# CAL_JIG.net
KiCad netlist of a schematic drawn in Altium Designer
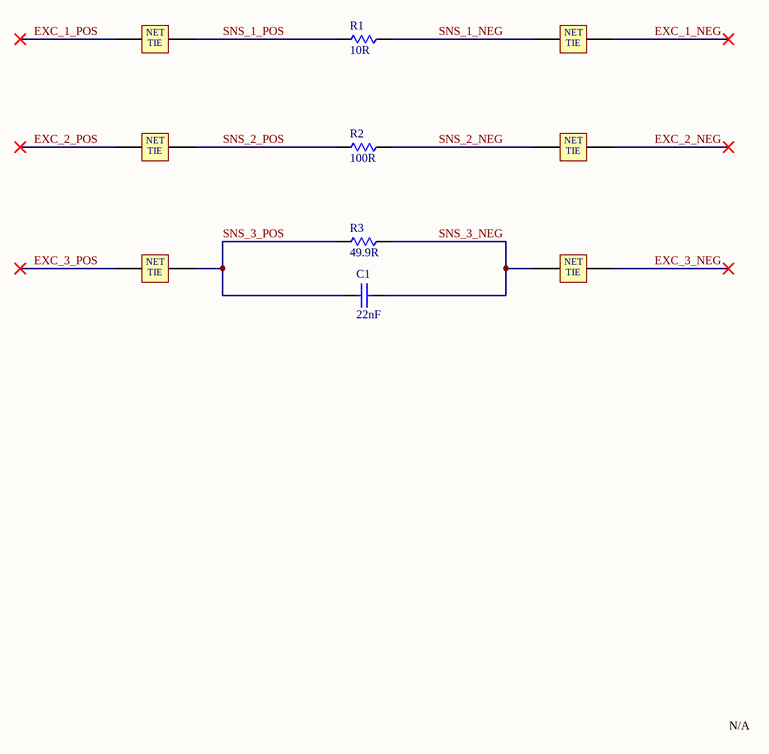
[diagram p0: CAL JIG.SchDoc]

(export (version "E")
  (design (tool "Eeschema 10.0.6"))
  (components
    (comp (ref "C1")
      (value "22nF")
      (footprint "0603-CAP")
      (description "CAP CER 470PF 50V NPO 0603")
      (libsource (lib "SGL_Capacitors") (part "Capacitor"))
    )
    (comp (ref "NT1")
      (value "Net Tie")
      (footprint "Net Tie 10mil")
      (description "Tying two nets")
      (libsource (lib "SGL_Misc") (part "Net Tie"))
    )
    (comp (ref "NT2")
      (value "Net Tie")
      (footprint "Net Tie 10mil")
      (description "Tying two nets")
      (libsource (lib "SGL_Misc") (part "Net Tie"))
    )
    (comp (ref "NT3")
      (value "Net Tie")
      (footprint "Net Tie 10mil")
      (description "Tying two nets")
      (libsource (lib "SGL_Misc") (part "Net Tie"))
    )
    (comp (ref "NT4")
      (value "Net Tie")
      (footprint "Net Tie 10mil")
      (description "Tying two nets")
      (libsource (lib "SGL_Misc") (part "Net Tie"))
    )
    (comp (ref "NT5")
      (value "Net Tie")
      (footprint "Net Tie 10mil")
      (description "Tying two nets")
      (libsource (lib "SGL_Misc") (part "Net Tie"))
    )
    (comp (ref "NT6")
      (value "Net Tie")
      (footprint "Net Tie 10mil")
      (description "Tying two nets")
      (libsource (lib "SGL_Misc") (part "Net Tie"))
    )
    (comp (ref "R1")
      (value "10R")
      (footprint "0603-RES")
      (description "RES SMD 1K OHM 1% 1/10W 0603")
      (libsource (lib "SGL_Resistives") (part "RESISTOR"))
    )
    (comp (ref "R2")
      (value "100R")
      (footprint "0603-RES")
      (description "RES SMD 1K OHM 1% 1/10W 0603")
      (libsource (lib "SGL_Resistives") (part "RESISTOR"))
    )
    (comp (ref "R3")
      (value "49.9R")
      (footprint "0603-RES")
      (description "RES SMD 1K OHM 1% 1/10W 0603")
      (libsource (lib "SGL_Resistives") (part "RESISTOR"))
    )
  )
  (nets
    (net (code "1") (name "/EXC_1_NEG") (class "Default")
      (node (ref "NT2") (pin "2") (pinfunction "2_2") (pintype "passive+no_connect"))
    )
    (net (code "2") (name "/EXC_1_POS") (class "Default")
      (node (ref "NT1") (pin "1") (pinfunction "1_1") (pintype "passive+no_connect"))
    )
    (net (code "3") (name "/EXC_2_NEG") (class "Default")
      (node (ref "NT4") (pin "2") (pinfunction "2_2") (pintype "passive+no_connect"))
    )
    (net (code "4") (name "/EXC_2_POS") (class "Default")
      (node (ref "NT3") (pin "1") (pinfunction "1_1") (pintype "passive+no_connect"))
    )
    (net (code "5") (name "/EXC_3_NEG") (class "Default")
      (node (ref "NT6") (pin "2") (pinfunction "2_2") (pintype "passive+no_connect"))
    )
    (net (code "6") (name "/EXC_3_POS") (class "Default")
      (node (ref "NT5") (pin "1") (pinfunction "1_1") (pintype "passive+no_connect"))
    )
    (net (code "7") (name "/SNS_1_NEG") (class "Default")
      (node (ref "NT2") (pin "1") (pinfunction "1_1") (pintype "passive"))
      (node (ref "R1") (pin "2") (pinfunction "2_2") (pintype "passive"))
    )
    (net (code "8") (name "/SNS_1_POS") (class "Default")
      (node (ref "NT1") (pin "2") (pinfunction "2_2") (pintype "passive"))
      (node (ref "R1") (pin "1") (pinfunction "1_1") (pintype "passive"))
    )
    (net (code "9") (name "/SNS_2_NEG") (class "Default")
      (node (ref "NT4") (pin "1") (pinfunction "1_1") (pintype "passive"))
      (node (ref "R2") (pin "2") (pinfunction "2_2") (pintype "passive"))
    )
    (net (code "10") (name "/SNS_2_POS") (class "Default")
      (node (ref "NT3") (pin "2") (pinfunction "2_2") (pintype "passive"))
      (node (ref "R2") (pin "1") (pinfunction "1_1") (pintype "passive"))
    )
    (net (code "11") (name "/SNS_3_NEG") (class "Default")
      (node (ref "C1") (pin "2") (pinfunction "2_2") (pintype "passive"))
      (node (ref "NT6") (pin "1") (pinfunction "1_1") (pintype "passive"))
      (node (ref "R3") (pin "2") (pinfunction "2_2") (pintype "passive"))
    )
    (net (code "12") (name "/SNS_3_POS") (class "Default")
      (node (ref "C1") (pin "1") (pinfunction "1_1") (pintype "passive"))
      (node (ref "NT5") (pin "2") (pinfunction "2_2") (pintype "passive"))
      (node (ref "R3") (pin "1") (pinfunction "1_1") (pintype "passive"))
    )
  )
)
